# MCU.net
KiCad netlist of a schematic drawn in Altium Designer
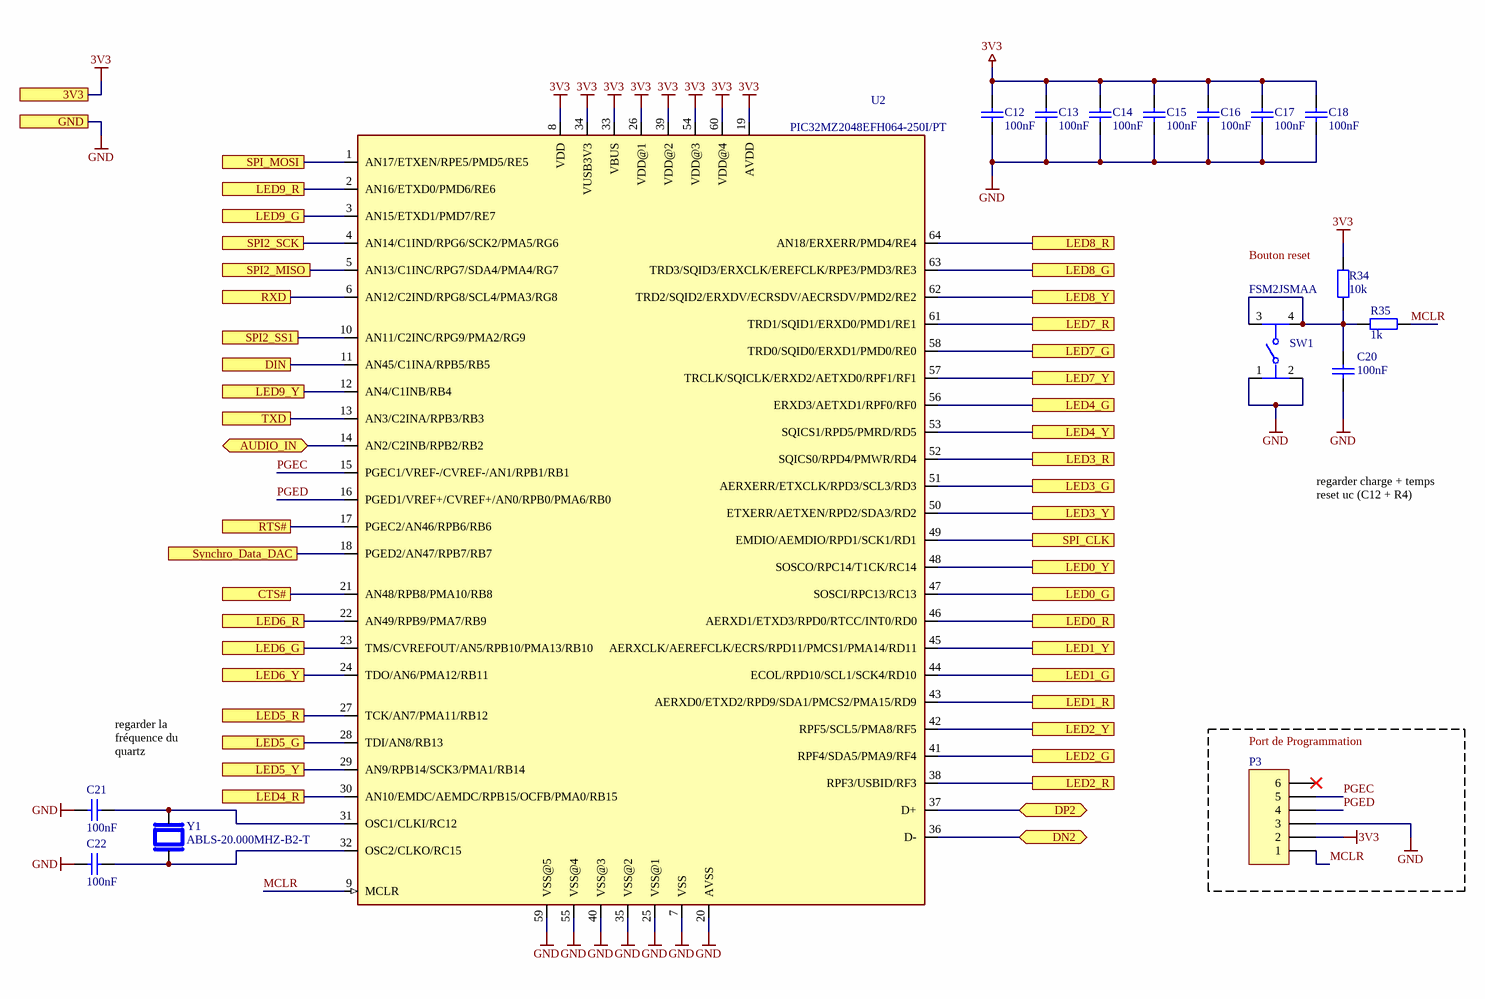
[diagram p0: MCU.SchDoc]

(export (version "E")
  (design (tool "Eeschema 10.0.6"))
  (components
    (comp (ref "C12")
      (value "100nF")
      (footprint "C0805")
      (description "Capacitor")
      (fields (field (name "PUBLISHER") "Altium Limited"))
      (libsource (lib "Miscellaneous Devices") (part "Cap"))
    )
    (comp (ref "C13")
      (value "100nF")
      (footprint "C0805")
      (description "Capacitor")
      (fields (field (name "PUBLISHER") "Altium Limited"))
      (libsource (lib "Miscellaneous Devices") (part "Cap"))
    )
    (comp (ref "C14")
      (value "100nF")
      (footprint "C0805")
      (description "Capacitor")
      (fields (field (name "PUBLISHER") "Altium Limited"))
      (libsource (lib "Miscellaneous Devices") (part "Cap"))
    )
    (comp (ref "C15")
      (value "100nF")
      (footprint "C0805")
      (description "Capacitor")
      (fields (field (name "PUBLISHER") "Altium Limited"))
      (libsource (lib "Miscellaneous Devices") (part "Cap"))
    )
    (comp (ref "C16")
      (value "100nF")
      (footprint "C0805")
      (description "Capacitor")
      (fields (field (name "PUBLISHER") "Altium Limited"))
      (libsource (lib "Miscellaneous Devices") (part "Cap"))
    )
    (comp (ref "C17")
      (value "100nF")
      (footprint "C0805")
      (description "Capacitor")
      (fields (field (name "PUBLISHER") "Altium Limited"))
      (libsource (lib "Miscellaneous Devices") (part "Cap"))
    )
    (comp (ref "C18")
      (value "100nF")
      (footprint "C0805")
      (description "Capacitor")
      (fields (field (name "PUBLISHER") "Altium Limited"))
      (libsource (lib "Miscellaneous Devices") (part "Cap"))
    )
    (comp (ref "C20")
      (value "100nF")
      (footprint "C0805")
      (description "10nf")
      (fields (field (name "PUBLISHER") "Altium Limited"))
      (libsource (lib "Miscellaneous Devices") (part "Cap"))
    )
    (comp (ref "C21")
      (value "100nF")
      (footprint "C0805")
      (description "10nf")
      (fields (field (name "PUBLISHER") "Altium Limited"))
      (libsource (lib "Miscellaneous Devices") (part "Cap"))
    )
    (comp (ref "C22")
      (value "100nF")
      (footprint "C0805")
      (description "10nf")
      (fields (field (name "PUBLISHER") "Altium Limited"))
      (libsource (lib "Miscellaneous Devices") (part "Cap"))
    )
    (comp (ref "P3")
      (value "76384-406LF")
      (footprint "HDR1X6")
      (description "Header, 6-Pin")
      (fields (field (name "PUBLISHER") "Altium Limited"))
      (libsource (lib "Miscellaneous Connectors") (part "Header 6"))
    )
    (comp (ref "R34")
      (value "10k")
      (footprint "RESC2012X06M")
      (description "Resistor")
      (fields (field (name "PUBLISHER") "Altium Limited"))
      (libsource (lib "Miscellaneous Devices") (part "Res2"))
    )
    (comp (ref "R35")
      (value "1k")
      (footprint "RESC2012X06M")
      (description "Resistor")
      (fields (field (name "PUBLISHER") "Altium Limited"))
      (libsource (lib "") (part "Res2_1"))
    )
    (comp (ref "SW1")
      (value "FSM2JSMAA")
      (footprint "FP-FSM2JSMAA-MFG")
      (description "SWITCH TACTILE SPST-NO 0.05A 24V")
      (fields
        (field (name "MANUFACTURER") "TE Connectivity")
        (field (name "OCTOPART") "https://octopart.com/fsm2jsmaa-te+connectivity-41720620")
      )
      (libsource (lib "Altium Content Vault") (part "b8895f3f4cefb76e1819d2863dba89b"))
    )
    (comp (ref "U2")
      (value "PIC32MZ2048EFH064-250I/PT")
      (footprint "QFP50P1200X1200X120-64N")
      (description "MIPS32Â® M-Class PICÂ® 32MZ Microcontroller IC 32-Bit 250MHz 2MB _2M x 8_ FLASH 64-TQFP _10x10_")
      (fields
        (field (name "MF") "Microchip")
        (field (name "DIGI-KEY_PART_NUMBER") "PIC32MZ2048EFH064-250I/PT-ND")
      )
      (libsource (lib "2225B_VumetreFrequenciel") (part "PIC32MZ2048EFH064-250I/PT"))
    )
    (comp (ref "Y1")
      (value "ABLS-20.000MHZ-B2-T")
      (footprint "XTAL_ABLS-20.000MHZ-B2-T")
      (description "HC/49US (AT49) SMD LOW PROFILE CRYSTAL")
      (fields (field (name "MF") "Abracon LLC"))
      (libsource (lib "2225B_VumetreFrequenciel") (part "ABLS-20.000MHZ-B2-T"))
    )
  )
  (nets
    (net (code "1") (name "/AUDIO_IN") (class "Default")
      (node (ref "U2") (pin "14") (pinfunction "AN2/C2INB/RPB2/RB2_14") (pintype "passive"))
    )
    (net (code "2") (name "/CTS#") (class "Default")
      (node (ref "U2") (pin "21") (pinfunction "AN48/RPB8/PMA10/RB8_21") (pintype "passive"))
    )
    (net (code "3") (name "/DIN") (class "Default")
      (node (ref "U2") (pin "11") (pinfunction "AN45/C1INA/RPB5/RB5_11") (pintype "passive"))
    )
    (net (code "4") (name "/DN2") (class "Default")
      (node (ref "U2") (pin "36") (pinfunction "D-_36") (pintype "passive"))
    )
    (net (code "5") (name "/DP2") (class "Default")
      (node (ref "U2") (pin "37") (pinfunction "D+_37") (pintype "passive"))
    )
    (net (code "6") (name "/LED0_G") (class "Default")
      (node (ref "U2") (pin "47") (pinfunction "SOSCI/RPC13/RC13_47") (pintype "passive"))
    )
    (net (code "7") (name "/LED0_R") (class "Default")
      (node (ref "U2") (pin "46") (pinfunction "AERXD1/ETXD3/RPD0/RTCC/INT0/RD0_46") (pintype "passive"))
    )
    (net (code "8") (name "/LED0_Y") (class "Default")
      (node (ref "U2") (pin "48") (pinfunction "SOSCO/RPC14/T1CK/RC14_48") (pintype "passive"))
    )
    (net (code "9") (name "/LED1_G") (class "Default")
      (node (ref "U2") (pin "44") (pinfunction "ECOL/RPD10/SCL1/SCK4/RD10_44") (pintype "passive"))
    )
    (net (code "10") (name "/LED1_R") (class "Default")
      (node (ref "U2") (pin "43") (pinfunction "AERXD0/ETXD2/RPD9/SDA1/PMCS2/PMA15/RD9_43") (pintype "passive"))
    )
    (net (code "11") (name "/LED1_Y") (class "Default")
      (node (ref "U2") (pin "45") (pinfunction "AERXCLK/AEREFCLK/ECRS/RPD11/PMCS1/PMA14/RD11_45") (pintype "passive"))
    )
    (net (code "12") (name "/LED2_G") (class "Default")
      (node (ref "U2") (pin "41") (pinfunction "RPF4/SDA5/PMA9/RF4_41") (pintype "passive"))
    )
    (net (code "13") (name "/LED2_R") (class "Default")
      (node (ref "U2") (pin "38") (pinfunction "RPF3/USBID/RF3_38") (pintype "passive"))
    )
    (net (code "14") (name "/LED2_Y") (class "Default")
      (node (ref "U2") (pin "42") (pinfunction "RPF5/SCL5/PMA8/RF5_42") (pintype "passive"))
    )
    (net (code "15") (name "/LED3_G") (class "Default")
      (node (ref "U2") (pin "51") (pinfunction "AERXERR/ETXCLK/RPD3/SCL3/RD3_51") (pintype "passive"))
    )
    (net (code "16") (name "/LED3_R") (class "Default")
      (node (ref "U2") (pin "52") (pinfunction "SQICS0/RPD4/PMWR/RD4_52") (pintype "passive"))
    )
    (net (code "17") (name "/LED3_Y") (class "Default")
      (node (ref "U2") (pin "50") (pinfunction "ETXERR/AETXEN/RPD2/SDA3/RD2_50") (pintype "passive"))
    )
    (net (code "18") (name "/LED4_G") (class "Default")
      (node (ref "U2") (pin "56") (pinfunction "ERXD3/AETXD1/RPF0/RF0_56") (pintype "passive"))
    )
    (net (code "19") (name "/LED4_R") (class "Default")
      (node (ref "U2") (pin "30") (pinfunction "AN10/EMDC/AEMDC/RPB15/OCFB/PMA0/RB15_30") (pintype "passive"))
    )
    (net (code "20") (name "/LED4_Y") (class "Default")
      (node (ref "U2") (pin "53") (pinfunction "SQICS1/RPD5/PMRD/RD5_53") (pintype "passive"))
    )
    (net (code "21") (name "/LED5_G") (class "Default")
      (node (ref "U2") (pin "28") (pinfunction "TDI/AN8/RB13_28") (pintype "passive"))
    )
    (net (code "22") (name "/LED5_R") (class "Default")
      (node (ref "U2") (pin "27") (pinfunction "TCK/AN7/PMA11/RB12_27") (pintype "passive"))
    )
    (net (code "23") (name "/LED5_Y") (class "Default")
      (node (ref "U2") (pin "29") (pinfunction "AN9/RPB14/SCK3/PMA1/RB14_29") (pintype "passive"))
    )
    (net (code "24") (name "/LED6_G") (class "Default")
      (node (ref "U2") (pin "23") (pinfunction "TMS/CVREFOUT/AN5/RPB10/PMA13/RB10_23") (pintype "passive"))
    )
    (net (code "25") (name "/LED6_R") (class "Default")
      (node (ref "U2") (pin "22") (pinfunction "AN49/RPB9/PMA7/RB9_22") (pintype "passive"))
    )
    (net (code "26") (name "/LED6_Y") (class "Default")
      (node (ref "U2") (pin "24") (pinfunction "TDO/AN6/PMA12/RB11_24") (pintype "passive"))
    )
    (net (code "27") (name "/LED7_G") (class "Default")
      (node (ref "U2") (pin "58") (pinfunction "TRD0/SQID0/ERXD1/PMD0/RE0_58") (pintype "passive"))
    )
    (net (code "28") (name "/LED7_R") (class "Default")
      (node (ref "U2") (pin "61") (pinfunction "TRD1/SQID1/ERXD0/PMD1/RE1_61") (pintype "passive"))
    )
    (net (code "29") (name "/LED7_Y") (class "Default")
      (node (ref "U2") (pin "57") (pinfunction "TRCLK/SQICLK/ERXD2/AETXD0/RPF1/RF1_57") (pintype "passive"))
    )
    (net (code "30") (name "/LED8_G") (class "Default")
      (node (ref "U2") (pin "63") (pinfunction "TRD3/SQID3/ERXCLK/EREFCLK/RPE3/PMD3/RE3_63") (pintype "passive"))
    )
    (net (code "31") (name "/LED8_R") (class "Default")
      (node (ref "U2") (pin "64") (pinfunction "AN18/ERXERR/PMD4/RE4_64") (pintype "passive"))
    )
    (net (code "32") (name "/LED8_Y") (class "Default")
      (node (ref "U2") (pin "62") (pinfunction "TRD2/SQID2/ERXDV/ECRSDV/AECRSDV/PMD2/RE2_62") (pintype "passive"))
    )
    (net (code "33") (name "/LED9_G") (class "Default")
      (node (ref "U2") (pin "3") (pinfunction "AN15/ETXD1/PMD7/RE7_3") (pintype "passive"))
    )
    (net (code "34") (name "/LED9_R") (class "Default")
      (node (ref "U2") (pin "2") (pinfunction "AN16/ETXD0/PMD6/RE6_2") (pintype "passive"))
    )
    (net (code "35") (name "/LED9_Y") (class "Default")
      (node (ref "U2") (pin "12") (pinfunction "AN4/C1INB/RB4_12") (pintype "passive"))
    )
    (net (code "36") (name "/MCLR") (class "Default")
      (node (ref "P3") (pin "1") (pinfunction "1_1") (pintype "passive"))
      (node (ref "R35") (pin "1") (pinfunction "1_1") (pintype "passive"))
      (node (ref "U2") (pin "9") (pinfunction "MCLR_9") (pintype "input"))
    )
    (net (code "37") (name "/PGEC") (class "Default")
      (node (ref "P3") (pin "5") (pinfunction "5_5") (pintype "passive"))
      (node (ref "U2") (pin "15") (pinfunction "PGEC1/VREF-/CVREF-/AN1/RPB1/RB1_15") (pintype "passive"))
    )
    (net (code "38") (name "/PGED") (class "Default")
      (node (ref "P3") (pin "4") (pinfunction "4_4") (pintype "passive"))
      (node (ref "U2") (pin "16") (pinfunction "PGED1/VREF+/CVREF+/AN0/RPB0/PMA6/RB0_16") (pintype "passive"))
    )
    (net (code "39") (name "/RTS#") (class "Default")
      (node (ref "U2") (pin "17") (pinfunction "PGEC2/AN46/RPB6/RB6_17") (pintype "passive"))
    )
    (net (code "40") (name "/RXD") (class "Default")
      (node (ref "U2") (pin "6") (pinfunction "AN12/C2IND/RPG8/SCL4/PMA3/RG8_6") (pintype "passive"))
    )
    (net (code "41") (name "/SPI2_MISO") (class "Default")
      (node (ref "U2") (pin "5") (pinfunction "AN13/C1INC/RPG7/SDA4/PMA4/RG7_5") (pintype "passive"))
    )
    (net (code "42") (name "/SPI2_SCK") (class "Default")
      (node (ref "U2") (pin "4") (pinfunction "AN14/C1IND/RPG6/SCK2/PMA5/RG6_4") (pintype "passive"))
    )
    (net (code "43") (name "/SPI2_SS1") (class "Default")
      (node (ref "U2") (pin "10") (pinfunction "AN11/C2INC/RPG9/PMA2/RG9_10") (pintype "passive"))
    )
    (net (code "44") (name "/SPI_CLK") (class "Default")
      (node (ref "U2") (pin "49") (pinfunction "EMDIO/AEMDIO/RPD1/SCK1/RD1_49") (pintype "passive"))
    )
    (net (code "45") (name "/SPI_MOSI") (class "Default")
      (node (ref "U2") (pin "1") (pinfunction "AN17/ETXEN/RPE5/PMD5/RE5_1") (pintype "passive"))
    )
    (net (code "46") (name "/Synchro_Data_DAC") (class "Default")
      (node (ref "U2") (pin "18") (pinfunction "PGED2/AN47/RPB7/RB7_18") (pintype "passive"))
    )
    (net (code "47") (name "/TXD") (class "Default")
      (node (ref "U2") (pin "13") (pinfunction "AN3/C2INA/RPB3/RB3_13") (pintype "passive"))
    )
    (net (code "48") (name "3V3") (class "Default")
      (node (ref "C12") (pin "1") (pinfunction "1_1") (pintype "passive"))
      (node (ref "C13") (pin "1") (pinfunction "1_1") (pintype "passive"))
      (node (ref "C14") (pin "1") (pinfunction "1_1") (pintype "passive"))
      (node (ref "C15") (pin "1") (pinfunction "1_1") (pintype "passive"))
      (node (ref "C16") (pin "1") (pinfunction "1_1") (pintype "passive"))
      (node (ref "C17") (pin "1") (pinfunction "1_1") (pintype "passive"))
      (node (ref "C18") (pin "1") (pinfunction "1_1") (pintype "passive"))
      (node (ref "P3") (pin "2") (pinfunction "2_2") (pintype "passive"))
      (node (ref "R34") (pin "1") (pinfunction "1_1") (pintype "passive"))
      (node (ref "U2") (pin "19") (pinfunction "AVDD_19") (pintype "power_in"))
      (node (ref "U2") (pin "26") (pinfunction "VDD@1_26") (pintype "power_in"))
      (node (ref "U2") (pin "33") (pinfunction "VBUS_33") (pintype "power_in"))
      (node (ref "U2") (pin "34") (pinfunction "VUSB3V3_34") (pintype "power_in"))
      (node (ref "U2") (pin "39") (pinfunction "VDD@2_39") (pintype "power_in"))
      (node (ref "U2") (pin "54") (pinfunction "VDD@3_54") (pintype "power_in"))
      (node (ref "U2") (pin "60") (pinfunction "VDD@4_60") (pintype "power_in"))
      (node (ref "U2") (pin "8") (pinfunction "VDD_8") (pintype "power_in"))
    )
    (net (code "49") (name "GND") (class "Default")
      (node (ref "C12") (pin "2") (pinfunction "2_2") (pintype "passive"))
      (node (ref "C13") (pin "2") (pinfunction "2_2") (pintype "passive"))
      (node (ref "C14") (pin "2") (pinfunction "2_2") (pintype "passive"))
      (node (ref "C15") (pin "2") (pinfunction "2_2") (pintype "passive"))
      (node (ref "C16") (pin "2") (pinfunction "2_2") (pintype "passive"))
      (node (ref "C17") (pin "2") (pinfunction "2_2") (pintype "passive"))
      (node (ref "C18") (pin "2") (pinfunction "2_2") (pintype "passive"))
      (node (ref "C20") (pin "1") (pinfunction "1_1") (pintype "passive"))
      (node (ref "C21") (pin "2") (pinfunction "2_2") (pintype "passive"))
      (node (ref "C22") (pin "2") (pinfunction "2_2") (pintype "passive"))
      (node (ref "P3") (pin "3") (pinfunction "3_3") (pintype "passive"))
      (node (ref "SW1") (pin "1") (pinfunction "1_1") (pintype "passive"))
      (node (ref "SW1") (pin "2") (pinfunction "2_2") (pintype "passive"))
      (node (ref "U2") (pin "20") (pinfunction "AVSS_20") (pintype "power_in"))
      (node (ref "U2") (pin "25") (pinfunction "VSS@1_25") (pintype "power_in"))
      (node (ref "U2") (pin "35") (pinfunction "VSS@2_35") (pintype "power_in"))
      (node (ref "U2") (pin "40") (pinfunction "VSS@3_40") (pintype "power_in"))
      (node (ref "U2") (pin "55") (pinfunction "VSS@4_55") (pintype "power_in"))
      (node (ref "U2") (pin "59") (pinfunction "VSS@5_59") (pintype "power_in"))
      (node (ref "U2") (pin "7") (pinfunction "VSS_7") (pintype "power_in"))
    )
    (net (code "50") (name "Net-(C20-Pad2)") (class "Default")
      (node (ref "C20") (pin "2") (pinfunction "2_2") (pintype "passive"))
      (node (ref "R34") (pin "2") (pinfunction "2_2") (pintype "passive"))
      (node (ref "R35") (pin "2") (pinfunction "2_2") (pintype "passive"))
      (node (ref "SW1") (pin "3") (pinfunction "3_3") (pintype "passive"))
      (node (ref "SW1") (pin "4") (pinfunction "4_4") (pintype "passive"))
    )
    (net (code "51") (name "Net-(U2-OSC1{slash}CLKI{slash}RC12)") (class "Default")
      (node (ref "C21") (pin "1") (pinfunction "1_1") (pintype "passive"))
      (node (ref "U2") (pin "31") (pinfunction "OSC1/CLKI/RC12_31") (pintype "passive"))
      (node (ref "Y1") (pin "2") (pinfunction "2_2") (pintype "passive"))
    )
    (net (code "52") (name "Net-(U2-OSC2{slash}CLKO{slash}RC15)") (class "Default")
      (node (ref "C22") (pin "1") (pinfunction "1_1") (pintype "passive"))
      (node (ref "U2") (pin "32") (pinfunction "OSC2/CLKO/RC15_32") (pintype "passive"))
      (node (ref "Y1") (pin "1") (pinfunction "1_1") (pintype "passive"))
    )
    (net (code "53") (name "unconnected-(P3-Pad6)") (class "Default")
      (node (ref "P3") (pin "6") (pinfunction "6_6") (pintype "passive+no_connect"))
    )
  )
)
